# main.net
KiCad netlist of a schematic drawn in EAGLE
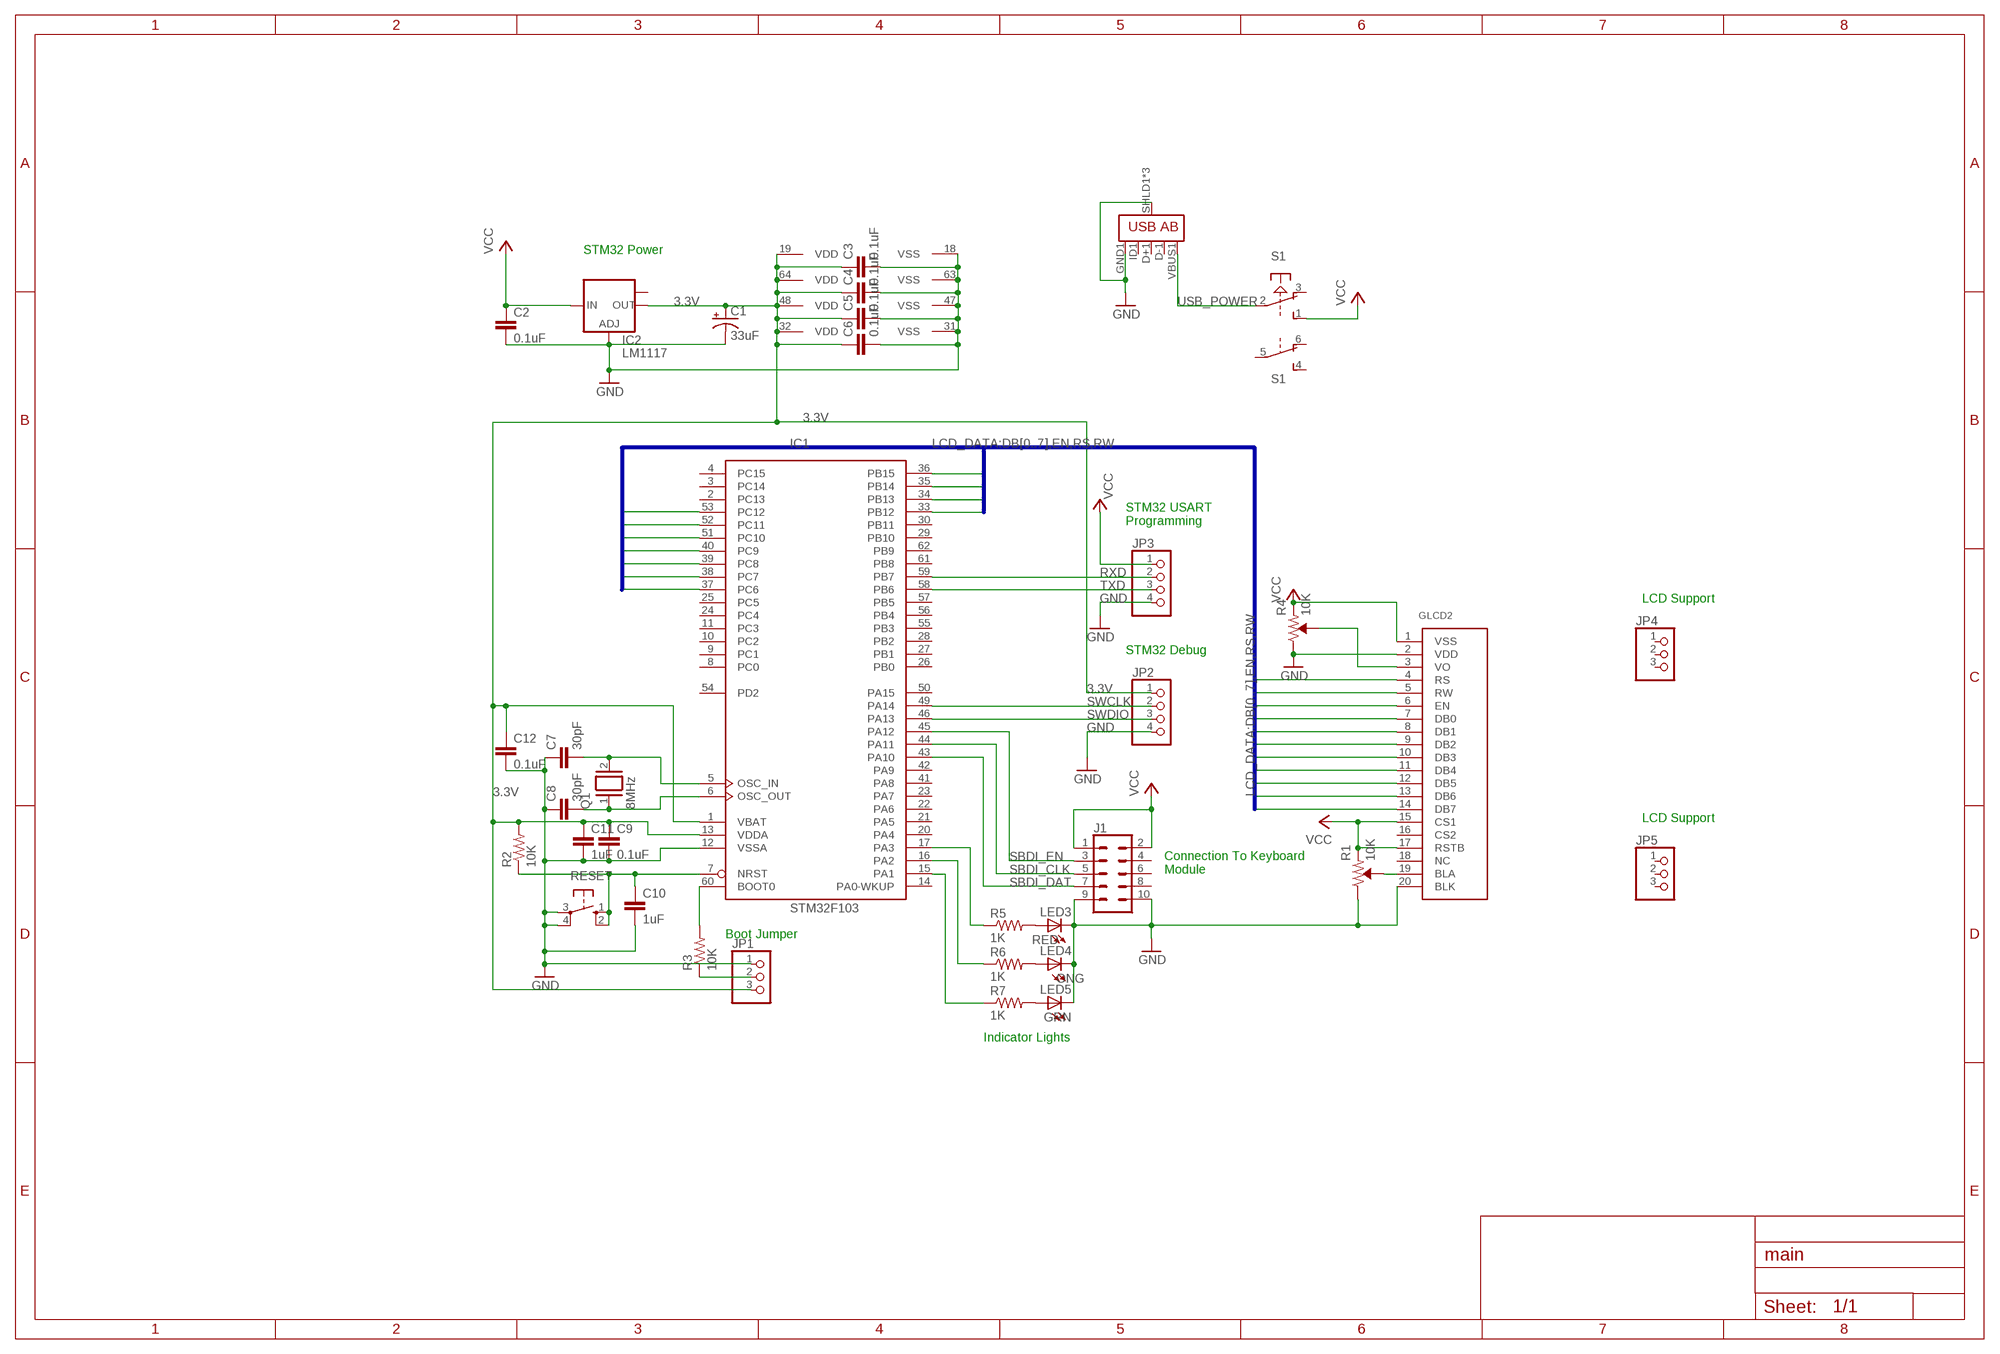
[diagram p0: schematic, sheet 1]

(export (version "E")
  (design (tool "Eeschema 10.0.6"))
  (components
    (comp (ref "C1")
      (value "33uF")
      (footprint "eagle-import:E2-5")
      (libsource (lib "eagle-import") (part "CPOL-USE2-5"))
    )
    (comp (ref "C2")
      (value "0.1uF")
      (footprint "eagle-import:C025-025X050")
      (libsource (lib "eagle-import") (part "C-EU025-025X050"))
    )
    (comp (ref "C3")
      (value "0.1uF")
      (footprint "eagle-import:C025-025X050")
      (libsource (lib "eagle-import") (part "C-EU025-025X050"))
    )
    (comp (ref "C4")
      (value "0.1uF")
      (footprint "eagle-import:C025-025X050")
      (libsource (lib "eagle-import") (part "C-EU025-025X050"))
    )
    (comp (ref "C5")
      (value "0.1uF")
      (footprint "eagle-import:C025-025X050")
      (libsource (lib "eagle-import") (part "C-EU025-025X050"))
    )
    (comp (ref "C6")
      (value "0.1uF")
      (footprint "eagle-import:C025-025X050")
      (libsource (lib "eagle-import") (part "C-EU025-025X050"))
    )
    (comp (ref "C7")
      (value "30pF")
      (footprint "eagle-import:C025-025X050")
      (libsource (lib "eagle-import") (part "C-EU025-025X050"))
    )
    (comp (ref "C8")
      (value "30pF")
      (footprint "eagle-import:C025-025X050")
      (libsource (lib "eagle-import") (part "C-EU025-025X050"))
    )
    (comp (ref "C9")
      (value "0.1uF")
      (footprint "eagle-import:C025-025X050")
      (libsource (lib "eagle-import") (part "C-EU025-025X050"))
    )
    (comp (ref "C10")
      (value "1uF")
      (footprint "eagle-import:C025-025X050")
      (libsource (lib "eagle-import") (part "C-EU025-025X050"))
    )
    (comp (ref "C11")
      (value "1uF")
      (footprint "eagle-import:C025-025X050")
      (libsource (lib "eagle-import") (part "C-EU025-025X050"))
    )
    (comp (ref "C12")
      (value "0.1uF")
      (footprint "eagle-import:C025-025X050")
      (libsource (lib "eagle-import") (part "C-EU025-025X050"))
    )
    (comp (ref "GLCD2")
      (value "LCD128X64")
      (footprint "eagle-import:GLCD_TRULY_128X64_20_PINES")
      (libsource (lib "eagle-import") (part "LCD128X64"))
    )
    (comp (ref "IC1")
      (value "STM32F103")
      (footprint "eagle-import:LQFP64")
      (libsource (lib "eagle-import") (part "STM32F103RTC"))
    )
    (comp (ref "IC2")
      (value "LM1117")
      (footprint "eagle-import:SOT223")
      (libsource (lib "eagle-import") (part "LM1117IMPX-ADJ"))
    )
    (comp (ref "J1")
      (value "CONN_05X2SHD_LOCK")
      (footprint "eagle-import:2X5-SHROUDED_LOCK")
      (libsource (lib "eagle-import") (part "CONN_05X2SHD_LOCK"))
    )
    (comp (ref "JP1")
      (value "PINHD-1X3")
      (footprint "eagle-import:1X03")
      (libsource (lib "eagle-import") (part "PINHD-1X3"))
    )
    (comp (ref "JP2")
      (value "PINHD-1X4")
      (footprint "eagle-import:1X04")
      (libsource (lib "eagle-import") (part "PINHD-1X4"))
    )
    (comp (ref "JP3")
      (value "PINHD-1X4")
      (footprint "eagle-import:1X04")
      (libsource (lib "eagle-import") (part "PINHD-1X4"))
    )
    (comp (ref "JP4")
      (value "PINHD-1X3")
      (footprint "eagle-import:1X03")
      (libsource (lib "eagle-import") (part "PINHD-1X3"))
    )
    (comp (ref "JP5")
      (value "PINHD-1X3")
      (footprint "eagle-import:1X03")
      (libsource (lib "eagle-import") (part "PINHD-1X3"))
    )
    (comp (ref "LED3")
      (value "RED")
      (footprint "eagle-import:LED5MM")
      (libsource (lib "eagle-import") (part "LED5MM"))
    )
    (comp (ref "LED4")
      (value "ONG")
      (footprint "eagle-import:LED5MM")
      (libsource (lib "eagle-import") (part "LED5MM"))
    )
    (comp (ref "LED5")
      (value "GRN")
      (footprint "eagle-import:LED5MM")
      (libsource (lib "eagle-import") (part "LED5MM"))
    )
    (comp (ref "Q1")
      (value "8MHz")
      (footprint "eagle-import:QS")
      (libsource (lib "eagle-import") (part "XTAL/S"))
    )
    (comp (ref "R1")
      (value "10K")
      (footprint "eagle-import:TRIMPOT-PTH-3386U")
      (libsource (lib "eagle-import") (part "TRIMPOT-KNOB"))
    )
    (comp (ref "R2")
      (value "10K")
      (footprint "eagle-import:0204_7")
      (libsource (lib "eagle-import") (part "R-US_0204/7"))
    )
    (comp (ref "R3")
      (value "10K")
      (footprint "eagle-import:0204_7")
      (libsource (lib "eagle-import") (part "R-US_0204/7"))
    )
    (comp (ref "R4")
      (value "10K")
      (footprint "eagle-import:TRIMPOT-PTH-3386U")
      (libsource (lib "eagle-import") (part "TRIMPOT-KNOB"))
    )
    (comp (ref "R5")
      (value "1K")
      (footprint "eagle-import:0204_7")
      (libsource (lib "eagle-import") (part "R-US_0204/7"))
    )
    (comp (ref "R6")
      (value "1K")
      (footprint "eagle-import:0204_7")
      (libsource (lib "eagle-import") (part "R-US_0204/7"))
    )
    (comp (ref "R7")
      (value "1K")
      (footprint "eagle-import:0204_7")
      (libsource (lib "eagle-import") (part "R-US_0204/7"))
    )
    (comp (ref "RESET")
      (value "10-XX")
      (footprint "eagle-import:B3F-10XX")
      (fields (field (name "MPN") "B3F-1000"))
      (libsource (lib "eagle-import") (part "10-XX"))
    )
    (comp (ref "S1")
      (value "PVA2R")
      (footprint "eagle-import:PVA2R")
      (libsource (lib "eagle-import") (part "PVA2R"))
    )
    (comp (ref "U1")
      (value "USB_AB_SMT")
      (footprint "eagle-import:USB-AB-MICRO-SMD")
      (libsource (lib "eagle-import") (part "USB_AB_SMT"))
    )
  )
  (nets
    (net (code "1") (name "/3.3V") (class "Default")
      (node (ref "C1") (pin "+") (pinfunction "+_+") (pintype "passive"))
      (node (ref "C11") (pin "1") (pinfunction "1_1") (pintype "passive"))
      (node (ref "C12") (pin "1") (pinfunction "1_1") (pintype "passive"))
      (node (ref "C3") (pin "1") (pinfunction "1_1") (pintype "passive"))
      (node (ref "C4") (pin "1") (pinfunction "1_1") (pintype "passive"))
      (node (ref "C5") (pin "1") (pinfunction "1_1") (pintype "passive"))
      (node (ref "C6") (pin "1") (pinfunction "1_1") (pintype "passive"))
      (node (ref "C9") (pin "1") (pinfunction "1_1") (pintype "passive"))
      (node (ref "IC1") (pin "1") (pinfunction "VBAT_1") (pintype "power_in"))
      (node (ref "IC1") (pin "13") (pinfunction "VDDA_13") (pintype "power_in"))
      (node (ref "IC1") (pin "19") (pinfunction "VDD_19") (pintype "power_in"))
      (node (ref "IC1") (pin "32") (pinfunction "VDD_32") (pintype "power_in"))
      (node (ref "IC1") (pin "48") (pinfunction "VDD_48") (pintype "power_in"))
      (node (ref "IC1") (pin "64") (pinfunction "VDD_64") (pintype "power_in"))
      (node (ref "IC2") (pin "2") (pinfunction "OUT_2") (pintype "passive"))
      (node (ref "JP1") (pin "3") (pinfunction "3_3") (pintype "passive"))
      (node (ref "JP2") (pin "1") (pinfunction "1_1") (pintype "passive"))
      (node (ref "R2") (pin "2") (pinfunction "2_2") (pintype "passive"))
    )
    (net (code "2") (name "/DB0") (class "Default")
      (node (ref "GLCD2") (pin "7") (pinfunction "DB0_7") (pintype "bidirectional"))
      (node (ref "IC1") (pin "33") (pinfunction "PB12_33") (pintype "bidirectional"))
    )
    (net (code "3") (name "/DB1") (class "Default")
      (node (ref "GLCD2") (pin "8") (pinfunction "DB1_8") (pintype "bidirectional"))
      (node (ref "IC1") (pin "34") (pinfunction "PB13_34") (pintype "bidirectional"))
    )
    (net (code "4") (name "/DB2") (class "Default")
      (node (ref "GLCD2") (pin "9") (pinfunction "DB2_9") (pintype "bidirectional"))
      (node (ref "IC1") (pin "35") (pinfunction "PB14_35") (pintype "bidirectional"))
    )
    (net (code "5") (name "/DB3") (class "Default")
      (node (ref "GLCD2") (pin "10") (pinfunction "DB3_10") (pintype "bidirectional"))
      (node (ref "IC1") (pin "36") (pinfunction "PB15_36") (pintype "bidirectional"))
    )
    (net (code "6") (name "/DB4") (class "Default")
      (node (ref "GLCD2") (pin "11") (pinfunction "DB4_11") (pintype "bidirectional"))
      (node (ref "IC1") (pin "37") (pinfunction "PC6_37") (pintype "bidirectional"))
    )
    (net (code "7") (name "/DB5") (class "Default")
      (node (ref "GLCD2") (pin "12") (pinfunction "DB5_12") (pintype "bidirectional"))
      (node (ref "IC1") (pin "38") (pinfunction "PC7_38") (pintype "bidirectional"))
    )
    (net (code "8") (name "/DB6") (class "Default")
      (node (ref "GLCD2") (pin "13") (pinfunction "DB6_13") (pintype "bidirectional"))
      (node (ref "IC1") (pin "39") (pinfunction "PC8_39") (pintype "bidirectional"))
    )
    (net (code "9") (name "/DB7") (class "Default")
      (node (ref "GLCD2") (pin "14") (pinfunction "DB7_14") (pintype "bidirectional"))
      (node (ref "IC1") (pin "40") (pinfunction "PC9_40") (pintype "bidirectional"))
    )
    (net (code "10") (name "/EN") (class "Default")
      (node (ref "GLCD2") (pin "6") (pinfunction "EN_6") (pintype "bidirectional"))
      (node (ref "IC1") (pin "53") (pinfunction "PC12_53") (pintype "bidirectional"))
    )
    (net (code "11") (name "/RS") (class "Default")
      (node (ref "GLCD2") (pin "4") (pinfunction "RS_4") (pintype "bidirectional"))
      (node (ref "IC1") (pin "51") (pinfunction "PC10_51") (pintype "bidirectional"))
    )
    (net (code "12") (name "/RW") (class "Default")
      (node (ref "GLCD2") (pin "5") (pinfunction "RW_5") (pintype "bidirectional"))
      (node (ref "IC1") (pin "52") (pinfunction "PC11_52") (pintype "bidirectional"))
    )
    (net (code "13") (name "/RXD") (class "Default")
      (node (ref "IC1") (pin "59") (pinfunction "PB7_59") (pintype "bidirectional"))
      (node (ref "JP3") (pin "2") (pinfunction "2_2") (pintype "passive"))
    )
    (net (code "14") (name "/SBDI_CLK") (class "Default")
      (node (ref "IC1") (pin "44") (pinfunction "PA11_44") (pintype "bidirectional"))
      (node (ref "J1") (pin "5") (pinfunction "5_5") (pintype "passive"))
    )
    (net (code "15") (name "/SBDI_DAT") (class "Default")
      (node (ref "IC1") (pin "43") (pinfunction "PA10_43") (pintype "bidirectional"))
      (node (ref "J1") (pin "7") (pinfunction "7_7") (pintype "passive"))
    )
    (net (code "16") (name "/SBDI_EN") (class "Default")
      (node (ref "IC1") (pin "45") (pinfunction "PA12_45") (pintype "bidirectional"))
      (node (ref "J1") (pin "3") (pinfunction "3_3") (pintype "passive"))
    )
    (net (code "17") (name "/SWCLK") (class "Default")
      (node (ref "IC1") (pin "49") (pinfunction "PA14_49") (pintype "bidirectional"))
      (node (ref "JP2") (pin "2") (pinfunction "2_2") (pintype "passive"))
    )
    (net (code "18") (name "/SWDIO") (class "Default")
      (node (ref "IC1") (pin "46") (pinfunction "PA13_46") (pintype "bidirectional"))
      (node (ref "JP2") (pin "3") (pinfunction "3_3") (pintype "passive"))
    )
    (net (code "19") (name "/TXD") (class "Default")
      (node (ref "IC1") (pin "58") (pinfunction "PB6_58") (pintype "bidirectional"))
      (node (ref "JP3") (pin "3") (pinfunction "3_3") (pintype "passive"))
    )
    (net (code "20") (name "/USB_POWER") (class "Default")
      (node (ref "S1") (pin "2") (pinfunction "P_2") (pintype "passive"))
      (node (ref "U1") (pin "VBUS1") (pinfunction "VBUS_VBUS1") (pintype "power_in"))
    )
    (net (code "22") (name "GND") (class "Default")
      (node (ref "C1") (pin "-") (pinfunction "-_-") (pintype "passive"))
      (node (ref "C10") (pin "2") (pinfunction "2_2") (pintype "passive"))
      (node (ref "C11") (pin "2") (pinfunction "2_2") (pintype "passive"))
      (node (ref "C12") (pin "2") (pinfunction "2_2") (pintype "passive"))
      (node (ref "C2") (pin "2") (pinfunction "2_2") (pintype "passive"))
      (node (ref "C3") (pin "2") (pinfunction "2_2") (pintype "passive"))
      (node (ref "C4") (pin "2") (pinfunction "2_2") (pintype "passive"))
      (node (ref "C5") (pin "2") (pinfunction "2_2") (pintype "passive"))
      (node (ref "C6") (pin "2") (pinfunction "2_2") (pintype "passive"))
      (node (ref "C7") (pin "1") (pinfunction "1_1") (pintype "passive"))
      (node (ref "C8") (pin "1") (pinfunction "1_1") (pintype "passive"))
      (node (ref "C9") (pin "2") (pinfunction "2_2") (pintype "passive"))
      (node (ref "GLCD2") (pin "2") (pinfunction "VDD_2") (pintype "power_in"))
      (node (ref "GLCD2") (pin "20") (pinfunction "BLK_20") (pintype "power_in"))
      (node (ref "IC1") (pin "12") (pinfunction "VSSA_12") (pintype "power_in"))
      (node (ref "IC1") (pin "18") (pinfunction "VSS_18") (pintype "power_in"))
      (node (ref "IC1") (pin "31") (pinfunction "VSS_31") (pintype "power_in"))
      (node (ref "IC1") (pin "47") (pinfunction "VSS_47") (pintype "power_in"))
      (node (ref "IC1") (pin "63") (pinfunction "VSS_63") (pintype "power_in"))
      (node (ref "IC2") (pin "1") (pinfunction "ADJ_1") (pintype "input"))
      (node (ref "J1") (pin "10") (pinfunction "10_10") (pintype "passive"))
      (node (ref "J1") (pin "9") (pinfunction "9_9") (pintype "passive"))
      (node (ref "JP1") (pin "1") (pinfunction "1_1") (pintype "passive"))
      (node (ref "JP2") (pin "4") (pinfunction "4_4") (pintype "passive"))
      (node (ref "JP3") (pin "4") (pinfunction "4_4") (pintype "passive"))
      (node (ref "LED3") (pin "K") (pinfunction "C_K") (pintype "passive"))
      (node (ref "LED4") (pin "K") (pinfunction "C_K") (pintype "passive"))
      (node (ref "LED5") (pin "K") (pinfunction "C_K") (pintype "passive"))
      (node (ref "R1") (pin "1") (pinfunction "1_1") (pintype "passive"))
      (node (ref "R4") (pin "1") (pinfunction "1_1") (pintype "passive"))
      (node (ref "RESET") (pin "3") (pinfunction "P_3") (pintype "passive"))
      (node (ref "RESET") (pin "4") (pinfunction "P1_4") (pintype "passive"))
      (node (ref "U1") (pin "GND1") (pinfunction "GND_GND1") (pintype "power_in"))
      (node (ref "U1") (pin "SHLD1") (pinfunction "SHIELD_SHLD1") (pintype "bidirectional"))
      (node (ref "U1") (pin "SHLD2") (pinfunction "SHIELD_SHLD2") (pintype "bidirectional"))
      (node (ref "U1") (pin "SHLD3") (pinfunction "SHIELD_SHLD3") (pintype "bidirectional"))
    )
    (net (code "23") (name "Net-(GLCD2-BLA)") (class "Default")
      (node (ref "GLCD2") (pin "19") (pinfunction "BLA_19") (pintype "power_in"))
      (node (ref "R1") (pin "2") (pinfunction "2_2") (pintype "passive"))
    )
    (net (code "24") (name "Net-(GLCD2-VO)") (class "Default")
      (node (ref "GLCD2") (pin "3") (pinfunction "VO_3") (pintype "bidirectional"))
      (node (ref "R4") (pin "2") (pinfunction "2_2") (pintype "passive"))
    )
    (net (code "25") (name "Net-(IC1A-BOOT0)") (class "Default")
      (node (ref "IC1") (pin "60") (pinfunction "BOOT0_60") (pintype "input"))
      (node (ref "R3") (pin "2") (pinfunction "2_2") (pintype "passive"))
    )
    (net (code "26") (name "Net-(IC1A-NRST)") (class "Default")
      (node (ref "C10") (pin "1") (pinfunction "1_1") (pintype "passive"))
      (node (ref "IC1") (pin "7") (pinfunction "NRST_7") (pintype "bidirectional"))
      (node (ref "R2") (pin "1") (pinfunction "1_1") (pintype "passive"))
      (node (ref "RESET") (pin "1") (pinfunction "S_1") (pintype "passive"))
      (node (ref "RESET") (pin "2") (pinfunction "S1_2") (pintype "passive"))
    )
    (net (code "27") (name "Net-(IC1A-OSC_IN)") (class "Default")
      (node (ref "C7") (pin "2") (pinfunction "2_2") (pintype "passive"))
      (node (ref "IC1") (pin "5") (pinfunction "OSC_IN_5") (pintype "bidirectional"))
      (node (ref "Q1") (pin "2") (pinfunction "2_2") (pintype "passive"))
    )
    (net (code "28") (name "Net-(IC1A-OSC_OUT)") (class "Default")
      (node (ref "C8") (pin "2") (pinfunction "2_2") (pintype "passive"))
      (node (ref "IC1") (pin "6") (pinfunction "OSC_OUT_6") (pintype "bidirectional"))
      (node (ref "Q1") (pin "1") (pinfunction "1_1") (pintype "passive"))
    )
    (net (code "29") (name "Net-(IC1A-PA1)") (class "Default")
      (node (ref "IC1") (pin "15") (pinfunction "PA1_15") (pintype "bidirectional"))
      (node (ref "R7") (pin "1") (pinfunction "1_1") (pintype "passive"))
    )
    (net (code "30") (name "Net-(IC1A-PA2)") (class "Default")
      (node (ref "IC1") (pin "16") (pinfunction "PA2_16") (pintype "bidirectional"))
      (node (ref "R6") (pin "1") (pinfunction "1_1") (pintype "passive"))
    )
    (net (code "31") (name "Net-(IC1A-PA3)") (class "Default")
      (node (ref "IC1") (pin "17") (pinfunction "PA3_17") (pintype "bidirectional"))
      (node (ref "R5") (pin "1") (pinfunction "1_1") (pintype "passive"))
    )
    (net (code "32") (name "Net-(JP1-Pad2)") (class "Default")
      (node (ref "JP1") (pin "2") (pinfunction "2_2") (pintype "passive"))
      (node (ref "R3") (pin "1") (pinfunction "1_1") (pintype "passive"))
    )
    (net (code "33") (name "Net-(LED3-PadA)") (class "Default")
      (node (ref "LED3") (pin "A") (pinfunction "A_A") (pintype "passive"))
      (node (ref "R5") (pin "2") (pinfunction "2_2") (pintype "passive"))
    )
    (net (code "34") (name "Net-(LED4-PadA)") (class "Default")
      (node (ref "LED4") (pin "A") (pinfunction "A_A") (pintype "passive"))
      (node (ref "R6") (pin "2") (pinfunction "2_2") (pintype "passive"))
    )
    (net (code "35") (name "Net-(LED5-PadA)") (class "Default")
      (node (ref "LED5") (pin "A") (pinfunction "A_A") (pintype "passive"))
      (node (ref "R7") (pin "2") (pinfunction "2_2") (pintype "passive"))
    )
    (net (code "36") (name "VCC") (class "Default")
      (node (ref "C2") (pin "1") (pinfunction "1_1") (pintype "passive"))
      (node (ref "GLCD2") (pin "1") (pinfunction "VSS_1") (pintype "power_in"))
      (node (ref "GLCD2") (pin "15") (pinfunction "CS1_15") (pintype "bidirectional"))
      (node (ref "GLCD2") (pin "17") (pinfunction "RSTB_17") (pintype "bidirectional"))
      (node (ref "IC2") (pin "3") (pinfunction "IN_3") (pintype "input"))
      (node (ref "J1") (pin "1") (pinfunction "1_1") (pintype "passive"))
      (node (ref "J1") (pin "2") (pinfunction "2_2") (pintype "passive"))
      (node (ref "JP3") (pin "1") (pinfunction "1_1") (pintype "passive"))
      (node (ref "R1") (pin "3") (pinfunction "3_3") (pintype "passive"))
      (node (ref "R4") (pin "3") (pinfunction "3_3") (pintype "passive"))
      (node (ref "S1") (pin "1") (pinfunction "S_1") (pintype "passive"))
    )
    (net (code "37") (name "unconnected-(GLCD2-CS2-Pad16)") (class "Default")
      (node (ref "GLCD2") (pin "16") (pinfunction "CS2_16") (pintype "bidirectional"))
    )
    (net (code "38") (name "unconnected-(GLCD2-NC-Pad18)") (class "Default")
      (node (ref "GLCD2") (pin "18") (pinfunction "NC_18") (pintype "bidirectional"))
    )
    (net (code "39") (name "unconnected-(IC1A-PA0-WKUP-Pad14)") (class "Default")
      (node (ref "IC1") (pin "14") (pinfunction "PA0-WKUP_14") (pintype "bidirectional"))
    )
    (net (code "40") (name "unconnected-(IC1A-PA4-Pad20)") (class "Default")
      (node (ref "IC1") (pin "20") (pinfunction "PA4_20") (pintype "bidirectional"))
    )
    (net (code "41") (name "unconnected-(IC1A-PA5-Pad21)") (class "Default")
      (node (ref "IC1") (pin "21") (pinfunction "PA5_21") (pintype "bidirectional"))
    )
    (net (code "42") (name "unconnected-(IC1A-PA6-Pad22)") (class "Default")
      (node (ref "IC1") (pin "22") (pinfunction "PA6_22") (pintype "bidirectional"))
    )
    (net (code "43") (name "unconnected-(IC1A-PA7-Pad23)") (class "Default")
      (node (ref "IC1") (pin "23") (pinfunction "PA7_23") (pintype "bidirectional"))
    )
    (net (code "44") (name "unconnected-(IC1A-PA8-Pad41)") (class "Default")
      (node (ref "IC1") (pin "41") (pinfunction "PA8_41") (pintype "bidirectional"))
    )
    (net (code "45") (name "unconnected-(IC1A-PA9-Pad42)") (class "Default")
      (node (ref "IC1") (pin "42") (pinfunction "PA9_42") (pintype "bidirectional"))
    )
    (net (code "46") (name "unconnected-(IC1A-PA15-Pad50)") (class "Default")
      (node (ref "IC1") (pin "50") (pinfunction "PA15_50") (pintype "bidirectional"))
    )
    (net (code "47") (name "unconnected-(IC1A-PB0-Pad26)") (class "Default")
      (node (ref "IC1") (pin "26") (pinfunction "PB0_26") (pintype "bidirectional"))
    )
    (net (code "48") (name "unconnected-(IC1A-PB1-Pad27)") (class "Default")
      (node (ref "IC1") (pin "27") (pinfunction "PB1_27") (pintype "bidirectional"))
    )
    (net (code "49") (name "unconnected-(IC1A-PB2-Pad28)") (class "Default")
      (node (ref "IC1") (pin "28") (pinfunction "PB2_28") (pintype "bidirectional"))
    )
    (net (code "50") (name "unconnected-(IC1A-PB3-Pad55)") (class "Default")
      (node (ref "IC1") (pin "55") (pinfunction "PB3_55") (pintype "bidirectional"))
    )
    (net (code "51") (name "unconnected-(IC1A-PB4-Pad56)") (class "Default")
      (node (ref "IC1") (pin "56") (pinfunction "PB4_56") (pintype "bidirectional"))
    )
    (net (code "52") (name "unconnected-(IC1A-PB5-Pad57)") (class "Default")
      (node (ref "IC1") (pin "57") (pinfunction "PB5_57") (pintype "bidirectional"))
    )
    (net (code "53") (name "unconnected-(IC1A-PB8-Pad61)") (class "Default")
      (node (ref "IC1") (pin "61") (pinfunction "PB8_61") (pintype "bidirectional"))
    )
    (net (code "54") (name "unconnected-(IC1A-PB9-Pad62)") (class "Default")
      (node (ref "IC1") (pin "62") (pinfunction "PB9_62") (pintype "bidirectional"))
    )
    (net (code "55") (name "unconnected-(IC1A-PB10-Pad29)") (class "Default")
      (node (ref "IC1") (pin "29") (pinfunction "PB10_29") (pintype "bidirectional"))
    )
    (net (code "56") (name "unconnected-(IC1A-PB11-Pad30)") (class "Default")
      (node (ref "IC1") (pin "30") (pinfunction "PB11_30") (pintype "bidirectional"))
    )
    (net (code "57") (name "unconnected-(IC1A-PC0-Pad8)") (class "Default")
      (node (ref "IC1") (pin "8") (pinfunction "PC0_8") (pintype "bidirectional"))
    )
    (net (code "58") (name "unconnected-(IC1A-PC1-Pad9)") (class "Default")
      (node (ref "IC1") (pin "9") (pinfunction "PC1_9") (pintype "bidirectional"))
    )
    (net (code "59") (name "unconnected-(IC1A-PC2-Pad10)") (class "Default")
      (node (ref "IC1") (pin "10") (pinfunction "PC2_10") (pintype "bidirectional"))
    )
    (net (code "60") (name "unconnected-(IC1A-PC3-Pad11)") (class "Default")
      (node (ref "IC1") (pin "11") (pinfunction "PC3_11") (pintype "bidirectional"))
    )
    (net (code "61") (name "unconnected-(IC1A-PC4-Pad24)") (class "Default")
      (node (ref "IC1") (pin "24") (pinfunction "PC4_24") (pintype "bidirectional"))
    )
    (net (code "62") (name "unconnected-(IC1A-PC5-Pad25)") (class "Default")
      (node (ref "IC1") (pin "25") (pinfunction "PC5_25") (pintype "bidirectional"))
    )
    (net (code "63") (name "unconnected-(IC1A-PC13-Pad2)") (class "Default")
      (node (ref "IC1") (pin "2") (pinfunction "PC13_2") (pintype "bidirectional"))
    )
    (net (code "64") (name "unconnected-(IC1A-PC14-Pad3)") (class "Default")
      (node (ref "IC1") (pin "3") (pinfunction "PC14_3") (pintype "bidirectional"))
    )
    (net (code "65") (name "unconnected-(IC1A-PC15-Pad4)") (class "Default")
      (node (ref "IC1") (pin "4") (pinfunction "PC15_4") (pintype "bidirectional"))
    )
    (net (code "66") (name "unconnected-(IC1A-PD2-Pad54)") (class "Default")
      (node (ref "IC1") (pin "54") (pinfunction "PD2_54") (pintype "bidirectional"))
    )
    (net (code "67") (name "unconnected-(IC2-OUT1-PadTAB)") (class "Default")
      (node (ref "IC2") (pin "TAB") (pinfunction "OUT1_TAB") (pintype "passive"))
    )
    (net (code "68") (name "unconnected-(J1-Pad4)") (class "Default")
      (node (ref "J1") (pin "4") (pinfunction "4_4") (pintype "passive"))
    )
    (net (code "69") (name "unconnected-(J1-Pad6)") (class "Default")
      (node (ref "J1") (pin "6") (pinfunction "6_6") (pintype "passive"))
    )
    (net (code "70") (name "unconnected-(J1-Pad8)") (class "Default")
      (node (ref "J1") (pin "8") (pinfunction "8_8") (pintype "passive"))
    )
    (net (code "71") (name "unconnected-(JP4-Pad1)") (class "Default")
      (node (ref "JP4") (pin "1") (pinfunction "1_1") (pintype "passive"))
    )
    (net (code "72") (name "unconnected-(JP4-Pad2)") (class "Default")
      (node (ref "JP4") (pin "2") (pinfunction "2_2") (pintype "passive"))
    )
    (net (code "73") (name "unconnected-(JP4-Pad3)") (class "Default")
      (node (ref "JP4") (pin "3") (pinfunction "3_3") (pintype "passive"))
    )
    (net (code "74") (name "unconnected-(JP5-Pad1)") (class "Default")
      (node (ref "JP5") (pin "1") (pinfunction "1_1") (pintype "passive"))
    )
    (net (code "75") (name "unconnected-(JP5-Pad2)") (class "Default")
      (node (ref "JP5") (pin "2") (pinfunction "2_2") (pintype "passive"))
    )
    (net (code "76") (name "unconnected-(JP5-Pad3)") (class "Default")
      (node (ref "JP5") (pin "3") (pinfunction "3_3") (pintype "passive"))
    )
    (net (code "77") (name "unconnected-(S1A-O-Pad3)") (class "Default")
      (node (ref "S1") (pin "3") (pinfunction "O_3") (pintype "passive"))
    )
    (net (code "78") (name "unconnected-(S1B-O-Pad6)") (class "Default")
      (node (ref "S1") (pin "6") (pinfunction "O_6") (pintype "passive"))
    )
    (net (code "79") (name "unconnected-(S1B-P-Pad5)") (class "Default")
      (node (ref "S1") (pin "5") (pinfunction "P_5") (pintype "passive"))
    )
    (net (code "80") (name "unconnected-(S1B-S-Pad4)") (class "Default")
      (node (ref "S1") (pin "4") (pinfunction "S_4") (pintype "passive"))
    )
    (net (code "81") (name "unconnected-(U1-D+-PadD+1)") (class "Default")
      (node (ref "U1") (pin "D+1") (pinfunction "D+_D+1") (pintype "bidirectional"))
    )
    (net (code "82") (name "unconnected-(U1-D--PadD-1)") (class "Default")
      (node (ref "U1") (pin "D-1") (pinfunction "D-_D-1") (pintype "bidirectional"))
    )
    (net (code "83") (name "unconnected-(U1-USBID-PadID1)") (class "Default")
      (node (ref "U1") (pin "ID1") (pinfunction "USBID_ID1") (pintype "bidirectional"))
    )
  )
)
